# sd_card_breakout.net
KiCad netlist of a schematic drawn in EAGLE
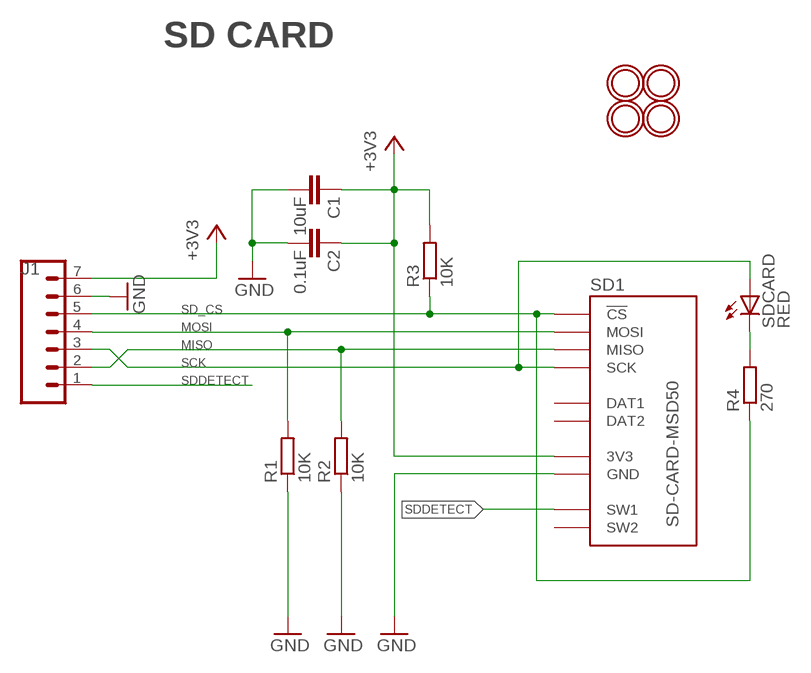
[diagram p0: schematic, sheet 1]

(export (version "E")
  (design (tool "Eeschema 10.0.6"))
  (components
    (comp (ref "C1")
      (value "10uF")
      (footprint "eagle-import:C0805K")
      (libsource (lib "eagle-import") (part "C-EUC0805K"))
    )
    (comp (ref "C2")
      (value "0.1uF")
      (footprint "eagle-import:C0805K")
      (libsource (lib "eagle-import") (part "C-EUC0805K"))
    )
    (comp (ref "J1")
      (value "CONN_07NO_SILK")
      (footprint "eagle-import:1X07_NO_SILK")
      (libsource (lib "eagle-import") (part "CONN_07NO_SILK"))
    )
    (comp (ref "MH1")
      (value "MOUNTINGHOLE2.5")
      (footprint "eagle-import:MOUNTINGHOLE_2.5_PLATED")
      (libsource (lib "eagle-import") (part "MOUNTINGHOLE2.5"))
    )
    (comp (ref "MH2")
      (value "MOUNTINGHOLE2.5")
      (footprint "eagle-import:MOUNTINGHOLE_2.5_PLATED")
      (libsource (lib "eagle-import") (part "MOUNTINGHOLE2.5"))
    )
    (comp (ref "MH3")
      (value "MOUNTINGHOLE2.5")
      (footprint "eagle-import:MOUNTINGHOLE_2.5_PLATED")
      (libsource (lib "eagle-import") (part "MOUNTINGHOLE2.5"))
    )
    (comp (ref "MH4")
      (value "MOUNTINGHOLE2.5")
      (footprint "eagle-import:MOUNTINGHOLE_2.5_PLATED")
      (libsource (lib "eagle-import") (part "MOUNTINGHOLE2.5"))
    )
    (comp (ref "R1")
      (value "10K")
      (footprint "eagle-import:R0805")
      (libsource (lib "eagle-import") (part "R-EU_R0805"))
    )
    (comp (ref "R2")
      (value "10K")
      (footprint "eagle-import:R0805")
      (libsource (lib "eagle-import") (part "R-EU_R0805"))
    )
    (comp (ref "R3")
      (value "10K")
      (footprint "eagle-import:R0805")
      (libsource (lib "eagle-import") (part "R-EU_R0805"))
    )
    (comp (ref "R4")
      (value "270")
      (footprint "eagle-import:R0805")
      (libsource (lib "eagle-import") (part "R-EU_R0805"))
    )
    (comp (ref "SD1")
      (value "SD-CARD-MSD50")
      (footprint "eagle-import:SD_5031821853")
      (libsource (lib "eagle-import") (part "SD-CARD-MSD50"))
    )
    (comp (ref "SDCARD")
      (value "RED")
      (footprint "eagle-import:CHIP-LED0805")
      (libsource (lib "eagle-import") (part "LEDCHIP-LED0805"))
    )
  )
  (nets
    (net (code "1") (name "+3V3") (class "Default")
      (node (ref "C1") (pin "1") (pinfunction "1_1") (pintype "passive"))
      (node (ref "C2") (pin "1") (pinfunction "1_1") (pintype "passive"))
      (node (ref "J1") (pin "7") (pinfunction "7_7") (pintype "passive"))
      (node (ref "R3") (pin "2") (pinfunction "2_2") (pintype "passive"))
      (node (ref "SD1") (pin "VCC") (pinfunction "3V3_VCC") (pintype "bidirectional"))
    )
    (net (code "2") (name "/MISO") (class "Default")
      (node (ref "J1") (pin "2") (pinfunction "2_2") (pintype "passive"))
      (node (ref "R2") (pin "2") (pinfunction "2_2") (pintype "passive"))
      (node (ref "SD1") (pin "MISO") (pinfunction "MISO_MISO") (pintype "bidirectional"))
    )
    (net (code "3") (name "/MOSI") (class "Default")
      (node (ref "J1") (pin "4") (pinfunction "4_4") (pintype "passive"))
      (node (ref "R1") (pin "2") (pinfunction "2_2") (pintype "passive"))
      (node (ref "SD1") (pin "MOSI") (pinfunction "MOSI_MOSI") (pintype "bidirectional"))
    )
    (net (code "4") (name "/SCK") (class "Default")
      (node (ref "J1") (pin "3") (pinfunction "3_3") (pintype "passive"))
      (node (ref "SD1") (pin "SCK") (pinfunction "SCK_SCK") (pintype "bidirectional"))
      (node (ref "SDCARD") (pin "A") (pinfunction "A_A") (pintype "passive"))
    )
    (net (code "5") (name "/SD_CS") (class "Default")
      (node (ref "J1") (pin "5") (pinfunction "5_5") (pintype "passive"))
      (node (ref "R3") (pin "1") (pinfunction "1_1") (pintype "passive"))
      (node (ref "R4") (pin "1") (pinfunction "1_1") (pintype "passive"))
      (node (ref "SD1") (pin "CS") (pinfunction "~{CS}_CS") (pintype "bidirectional"))
    )
    (net (code "6") (name "GND") (class "Default")
      (node (ref "C1") (pin "2") (pinfunction "2_2") (pintype "passive"))
      (node (ref "C2") (pin "2") (pinfunction "2_2") (pintype "passive"))
      (node (ref "J1") (pin "6") (pinfunction "6_6") (pintype "passive"))
      (node (ref "R1") (pin "1") (pinfunction "1_1") (pintype "passive"))
      (node (ref "R2") (pin "1") (pinfunction "1_1") (pintype "passive"))
      (node (ref "SD1") (pin "GND") (pinfunction "GND_GND") (pintype "bidirectional"))
    )
    (net (code "7") (name "Net-(R4-Pad2)") (class "Default")
      (node (ref "R4") (pin "2") (pinfunction "2_2") (pintype "passive"))
      (node (ref "SDCARD") (pin "C") (pinfunction "C_C") (pintype "passive"))
    )
    (net (code "8") (name "SDDETECT") (class "Default")
      (node (ref "J1") (pin "1") (pinfunction "1_1") (pintype "passive"))
      (node (ref "SD1") (pin "SW1") (pinfunction "SW1_SW1") (pintype "bidirectional"))
    )
    (net (code "9") (name "unconnected-(SD1-PadDAT1)") (class "Default")
      (node (ref "SD1") (pin "DAT1") (pinfunction "DAT1_DAT1") (pintype "bidirectional"))
    )
    (net (code "10") (name "unconnected-(SD1-PadDAT2)") (class "Default")
      (node (ref "SD1") (pin "DAT2") (pinfunction "DAT2_DAT2") (pintype "bidirectional"))
    )
    (net (code "11") (name "unconnected-(SD1-PadSW2)") (class "Default")
      (node (ref "SD1") (pin "SW2") (pinfunction "SW2_SW2") (pintype "bidirectional"))
    )
  )
)
